# SCH_MasterNodeV3_2024-03-10.net
KiCad netlist of a schematic drawn in EasyEDA
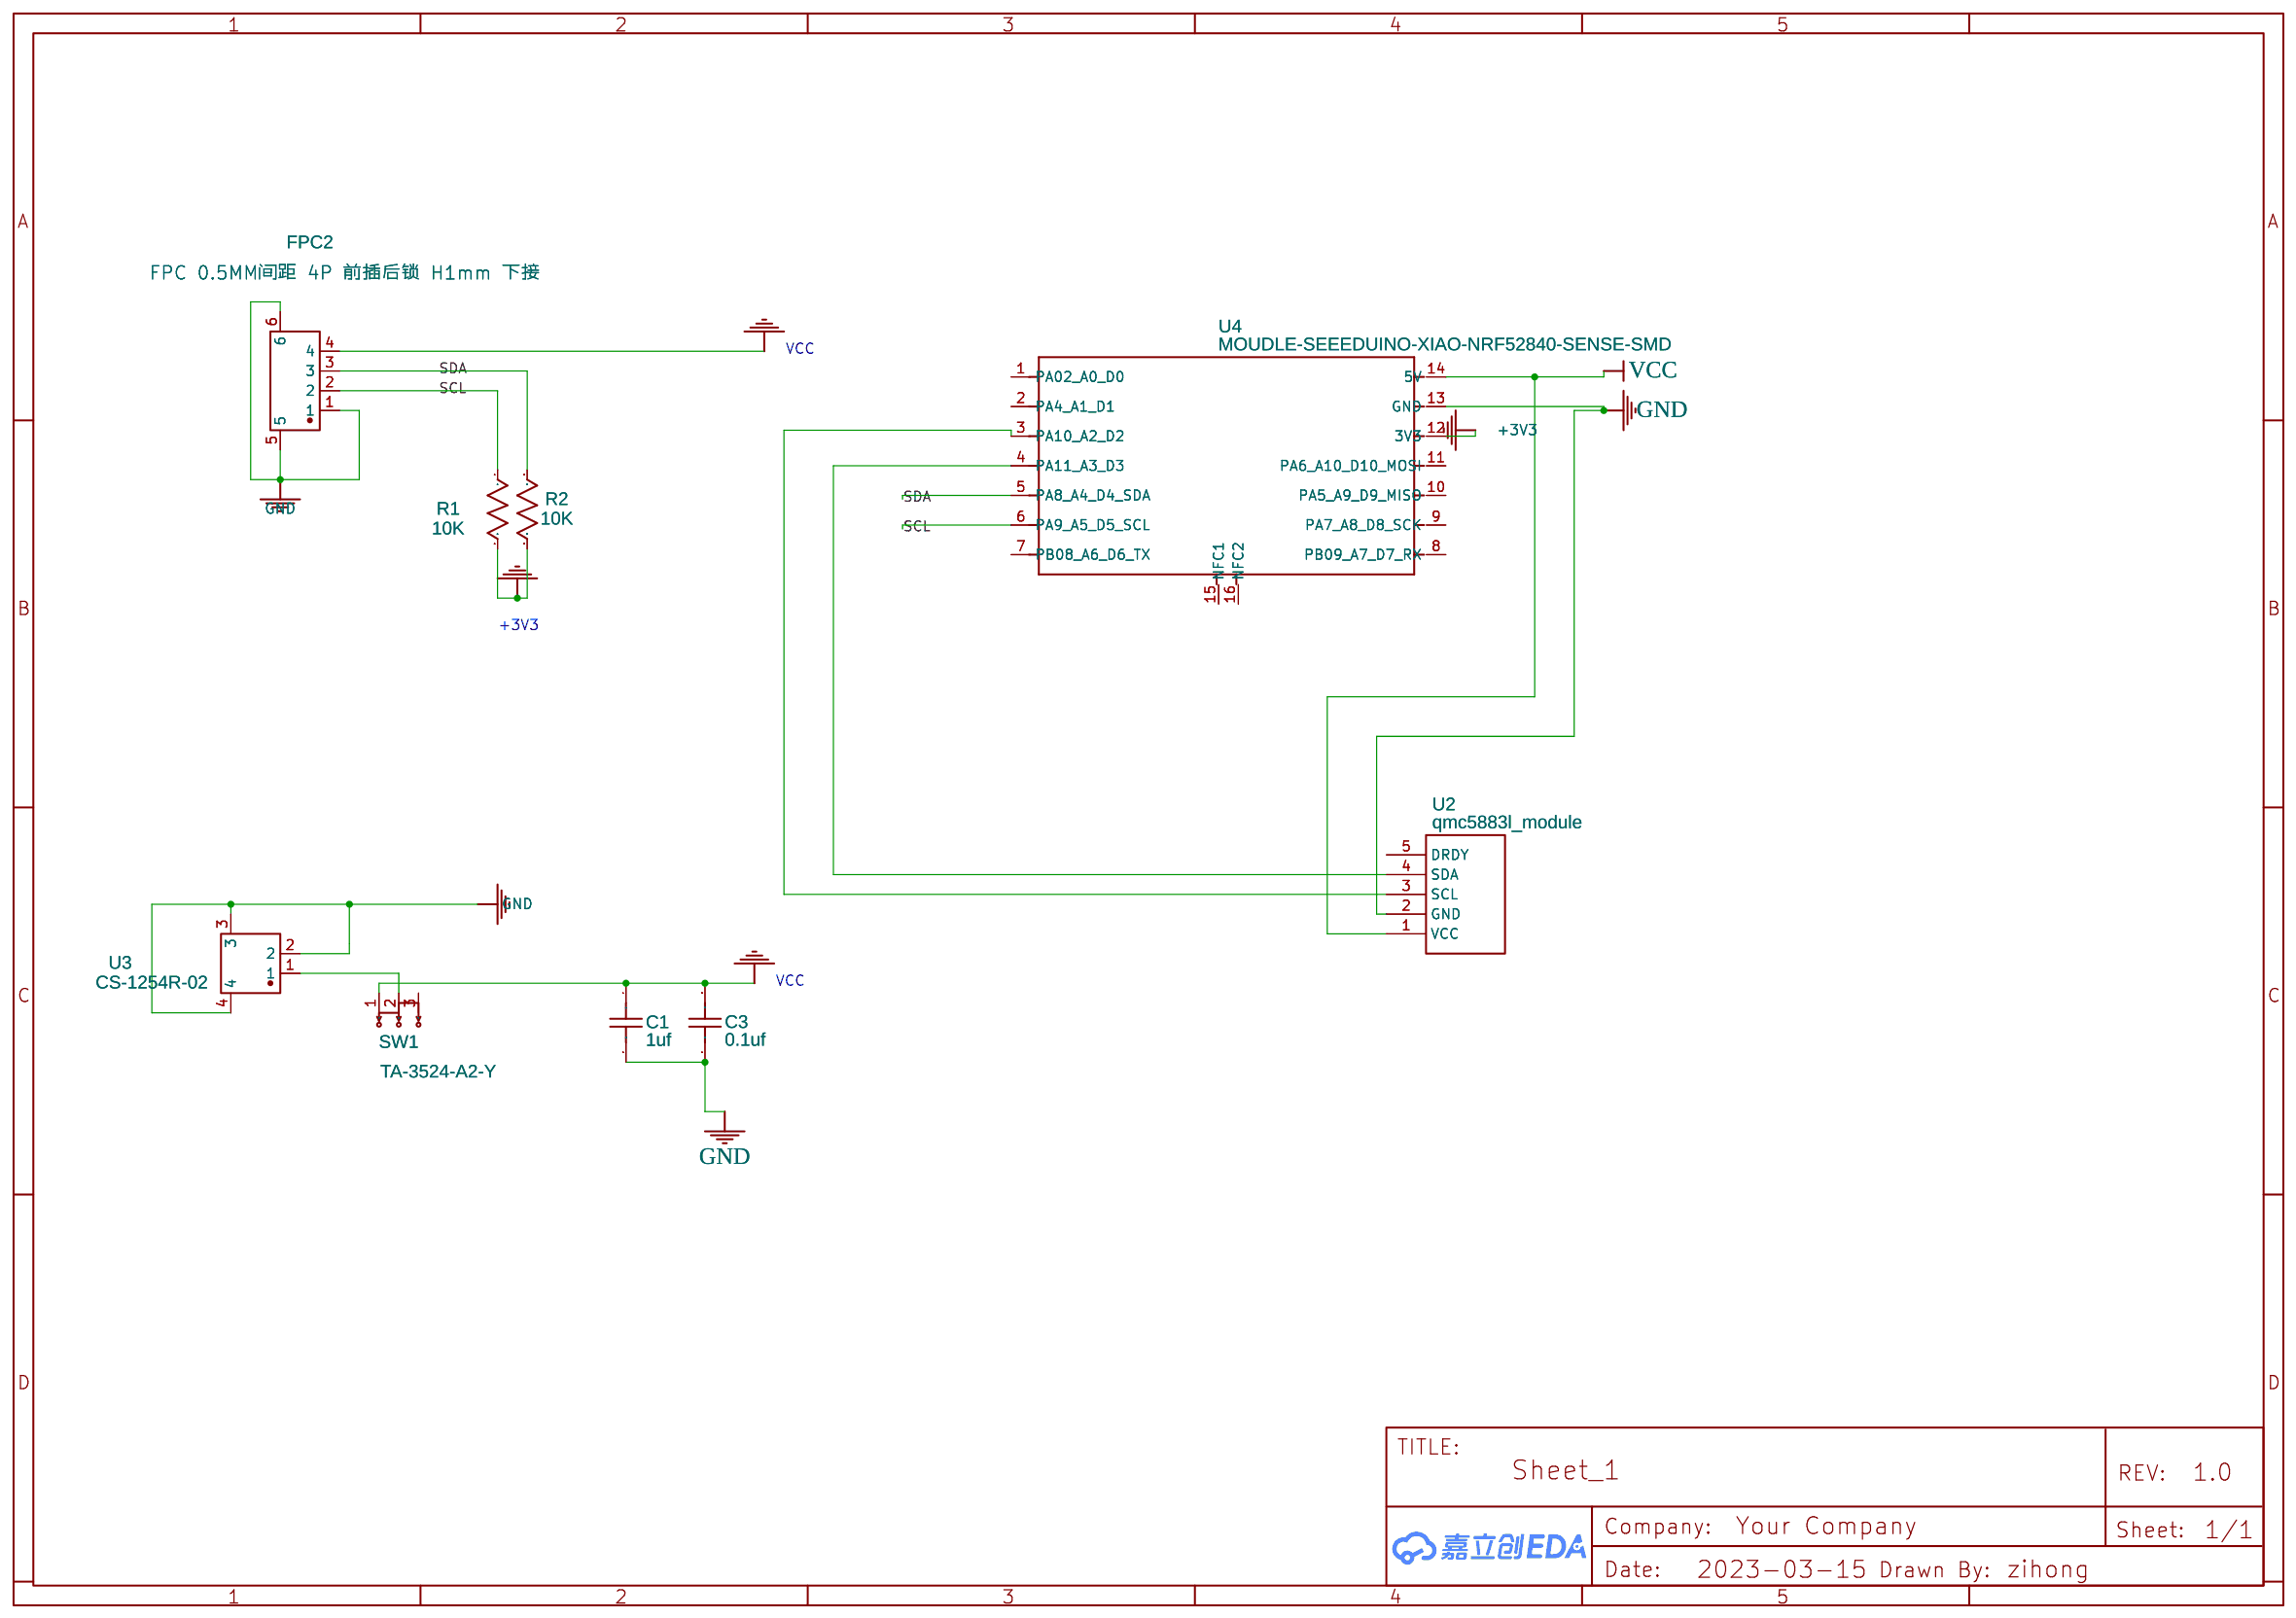
[diagram p0: schematic sheet]

(export (version "E")
  (design (tool "Eeschema 10.0.6"))
  (components
    (comp (ref "C1") (value "1uf") (libsource (lib "") (part "C_0402_US")))
    (comp (ref "C3") (value "0.1uf") (libsource (lib "") (part "C_0402_US_1")))
    (comp (ref "FPC2")
      (value "FPC 0.5MM间距 4P 前插后锁 H1mm 下接")
      (fields
        (field (name "BOM_Manufacturer Part") "FPC 0.5MM 4P 翻盖式 H2.0")
        (field (name "BOM_Supplier Part") "C9345")
      )
      (libsource (lib "") (part "FPC 0.5MM 4P 翻盖式 H2.0"))
    )
    (comp (ref "R1") (value "10K") (libsource (lib "") (part "R_0402_US")))
    (comp (ref "R2") (value "10K") (libsource (lib "") (part "R_0402_US")))
    (comp (ref "SW1")
      (value "TA-3524-A2-Y")
      (fields (field (name "BOM_Supplier Part") "C842774"))
      (libsource (lib "") (part "TA-3524-A2-Y"))
    )
    (comp (ref "U2") (value "qmc5883l_module") (libsource (lib "") (part "qmc5883l_module")))
    (comp (ref "U3")
      (value "CS-1254R-02")
      (fields (field (name "BOM_Supplier Part") "C5142894"))
      (libsource (lib "") (part "CS-1254R-02"))
    )
    (comp (ref "U4")
      (value "MOUDLE-SEEEDUINO-XIAO-NRF52840-SENSE-SMD")
      (libsource (lib "") (part "MOUDLE-SEEEDUINO-XIAO-NRF52840-SENSE-SMD"))
    )
  )
  (nets
    (net (code "1") (name "+3V3") (class "Default")
      (node (ref "R1") (pin "2") (pinfunction "2_2") (pintype "unspecified"))
      (node (ref "R2") (pin "2") (pinfunction "2_2") (pintype "unspecified"))
      (node (ref "U4") (pin "12") (pinfunction "3V3_12") (pintype "bidirectional"))
    )
    (net (code "2") (name "/SCL") (class "Default")
      (node (ref "FPC2") (pin "2") (pinfunction "2_2") (pintype "unspecified"))
      (node (ref "R1") (pin "1") (pinfunction "1_1") (pintype "unspecified"))
      (node (ref "U4") (pin "6") (pinfunction "PA9_A5_D5_SCL_6") (pintype "bidirectional"))
    )
    (net (code "3") (name "/SDA") (class "Default")
      (node (ref "FPC2") (pin "3") (pinfunction "3_3") (pintype "unspecified"))
      (node (ref "R2") (pin "1") (pinfunction "1_1") (pintype "unspecified"))
      (node (ref "U4") (pin "5") (pinfunction "PA8_A4_D4_SDA_5") (pintype "bidirectional"))
    )
    (net (code "4") (name "GND") (class "Default")
      (node (ref "C1") (pin "2") (pinfunction "2_2") (pintype "unspecified"))
      (node (ref "C3") (pin "1") (pinfunction "1_1") (pintype "unspecified"))
      (node (ref "FPC2") (pin "1") (pinfunction "1_1") (pintype "unspecified"))
      (node (ref "FPC2") (pin "5") (pinfunction "5_5") (pintype "unspecified"))
      (node (ref "FPC2") (pin "6") (pinfunction "6_6") (pintype "unspecified"))
      (node (ref "U2") (pin "2") (pinfunction "GND_2") (pintype "unspecified"))
      (node (ref "U3") (pin "2") (pinfunction "2_2") (pintype "unspecified"))
      (node (ref "U3") (pin "3") (pinfunction "3_3") (pintype "unspecified"))
      (node (ref "U3") (pin "4") (pinfunction "4_4") (pintype "unspecified"))
      (node (ref "U4") (pin "13") (pinfunction "GND_13") (pintype "bidirectional"))
    )
    (net (code "5") (name "Net-(SW1-Pad2)") (class "Default")
      (node (ref "SW1") (pin "2") (pinfunction "2_2") (pintype "unspecified"))
      (node (ref "U3") (pin "1") (pinfunction "1_1") (pintype "unspecified"))
    )
    (net (code "6") (name "Net-(U2-SCL)") (class "Default")
      (node (ref "U2") (pin "3") (pinfunction "SCL_3") (pintype "unspecified"))
      (node (ref "U4") (pin "3") (pinfunction "PA10_A2_D2_3") (pintype "bidirectional"))
    )
    (net (code "7") (name "Net-(U2-SDA)") (class "Default")
      (node (ref "U2") (pin "4") (pinfunction "SDA_4") (pintype "unspecified"))
      (node (ref "U4") (pin "4") (pinfunction "PA11_A3_D3_4") (pintype "bidirectional"))
    )
    (net (code "8") (name "VCC") (class "Default")
      (node (ref "C1") (pin "1") (pinfunction "1_1") (pintype "unspecified"))
      (node (ref "C3") (pin "2") (pinfunction "2_2") (pintype "unspecified"))
      (node (ref "FPC2") (pin "4") (pinfunction "4_4") (pintype "unspecified"))
      (node (ref "SW1") (pin "1") (pinfunction "1_1") (pintype "unspecified"))
      (node (ref "U2") (pin "1") (pinfunction "VCC_1") (pintype "unspecified"))
      (node (ref "U4") (pin "14") (pinfunction "5V_14") (pintype "bidirectional"))
    )
    (net (code "9") (name "unconnected-(SW1-Pad3)") (class "Default")
      (node (ref "SW1") (pin "3") (pinfunction "3_3") (pintype "unspecified"))
    )
    (net (code "10") (name "unconnected-(U2-DRDY-Pad5)") (class "Default")
      (node (ref "U2") (pin "5") (pinfunction "DRDY_5") (pintype "unspecified"))
    )
    (net (code "11") (name "unconnected-(U4-NFC1-Pad15)") (class "Default")
      (node (ref "U4") (pin "15") (pinfunction "NFC1_15") (pintype "bidirectional"))
    )
    (net (code "12") (name "unconnected-(U4-NFC2-Pad16)") (class "Default")
      (node (ref "U4") (pin "16") (pinfunction "NFC2_16") (pintype "bidirectional"))
    )
    (net (code "13") (name "unconnected-(U4-PA02_A0_D0-Pad1)") (class "Default")
      (node (ref "U4") (pin "1") (pinfunction "PA02_A0_D0_1") (pintype "bidirectional"))
    )
    (net (code "14") (name "unconnected-(U4-PA4_A1_D1-Pad2)") (class "Default")
      (node (ref "U4") (pin "2") (pinfunction "PA4_A1_D1_2") (pintype "bidirectional"))
    )
    (net (code "15") (name "unconnected-(U4-PA5_A9_D9_MISO-Pad10)") (class "Default")
      (node (ref "U4") (pin "10") (pinfunction "PA5_A9_D9_MISO_10") (pintype "bidirectional"))
    )
    (net (code "16") (name "unconnected-(U4-PA6_A10_D10_MOSI-Pad11)") (class "Default")
      (node (ref "U4") (pin "11") (pinfunction "PA6_A10_D10_MOSI_11") (pintype "bidirectional"))
    )
    (net (code "17") (name "unconnected-(U4-PA7_A8_D8_SCK-Pad9)") (class "Default")
      (node (ref "U4") (pin "9") (pinfunction "PA7_A8_D8_SCK_9") (pintype "bidirectional"))
    )
    (net (code "18") (name "unconnected-(U4-PB08_A6_D6_TX-Pad7)") (class "Default")
      (node (ref "U4") (pin "7") (pinfunction "PB08_A6_D6_TX_7") (pintype "bidirectional"))
    )
    (net (code "19") (name "unconnected-(U4-PB09_A7_D7_RX-Pad8)") (class "Default")
      (node (ref "U4") (pin "8") (pinfunction "PB09_A7_D7_RX_8") (pintype "bidirectional"))
    )
  )
)
